# PowerSupply.net
KiCad netlist of a schematic drawn in Altium Designer
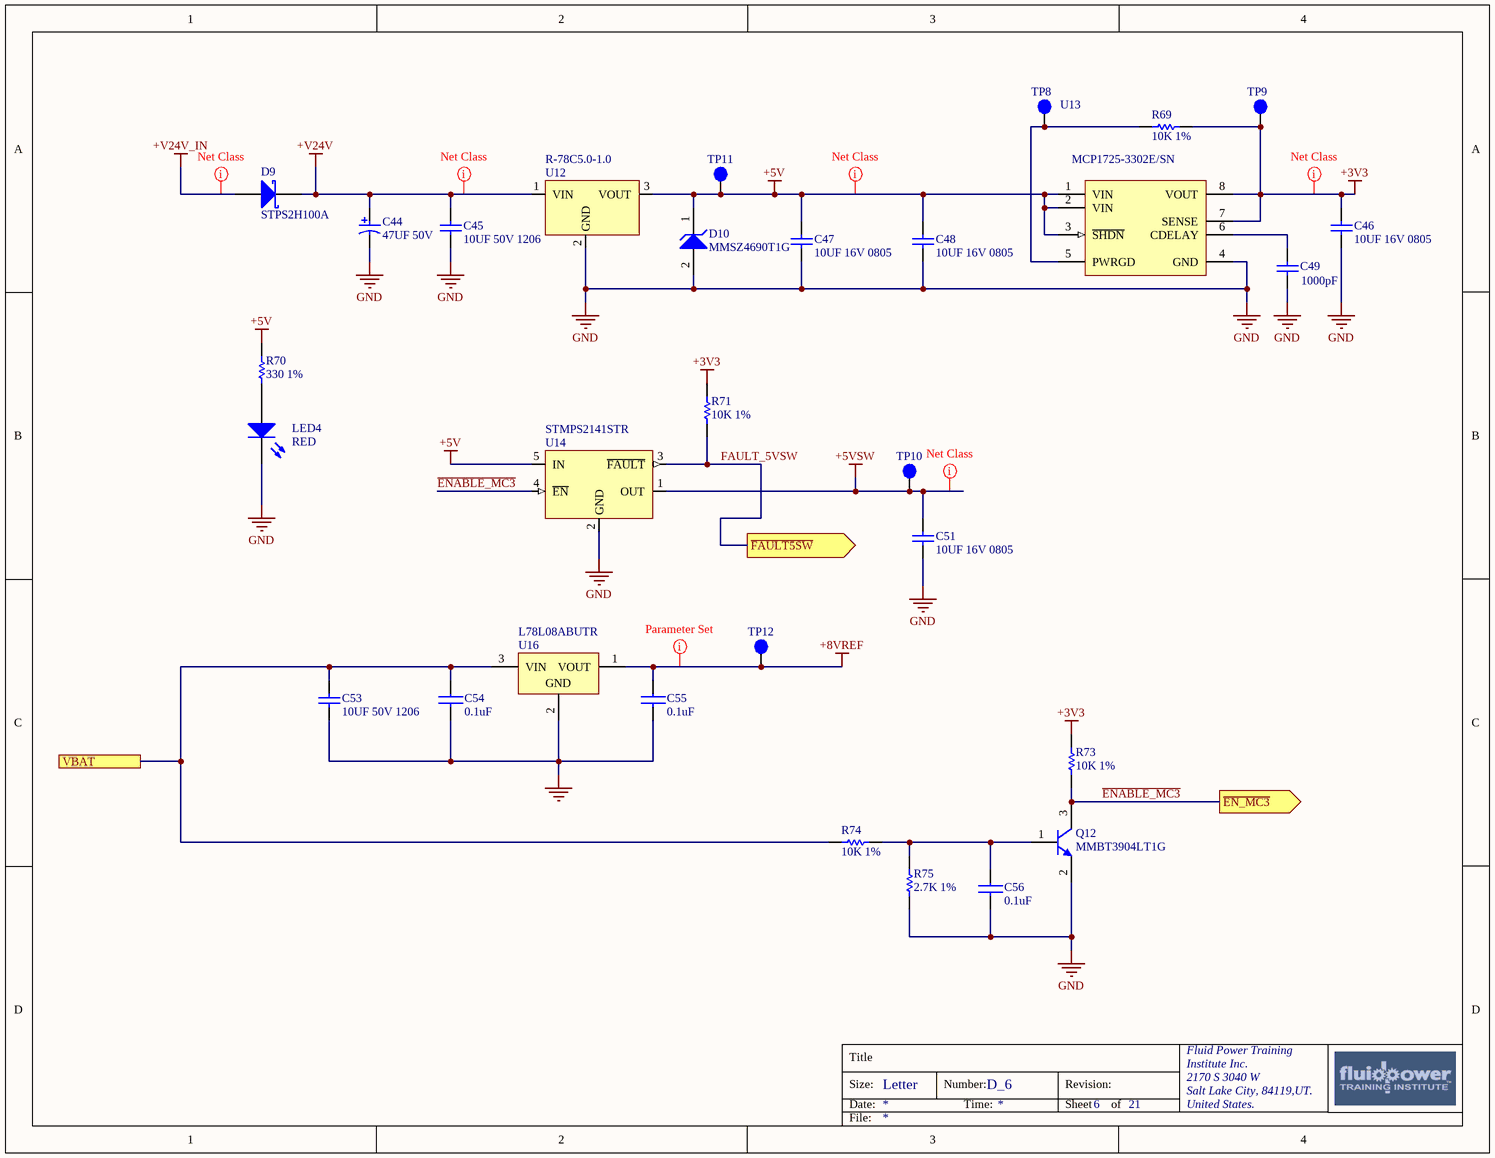
[diagram p0: PowerSupply.SchDoc]

(export (version "E")
  (design (tool "Eeschema 10.0.6"))
  (components
    (comp (ref "C44")
      (value "47UF 50V")
      (footprint "MC1:PNSC-EEE-HA1H470XP-2_V")
      (description "EEE-HA Series 50 V 47 uF Ø 6.3 x 7.7 mm 105 °C SMT V-Chip Aluminum Electrolytic")
      (fields
        (field (name "MANUFACTURER") "Panasonic")
        (field (name "MANUFACTURER PART NUMBER") "EEE-HA1H470XP")
      )
      (libsource (lib "MC1") (part "EEE-HA1H470XP"))
    )
    (comp (ref "C45")
      (value "10UF 50V 1206")
      (footprint "MC1:CAPC3216X180X20ML20")
      (description "CAP CER 10UF 50V X5R 1206")
      (fields
        (field (name "MANUFACTURER") "TDK")
        (field (name "MANUFACTURER PART NUMBER") "C3216X5R1H106K160AB")
      )
      (libsource (lib "MC1") (part "C3216X5R1H106K160AB"))
    )
    (comp (ref "C46")
      (value "10UF 16V 0805")
      (footprint "MC1:CAPC2012X14M")
      (description "CAP CER 10UF 16V X5R 0805")
      (fields
        (field (name "MANUFACTURER") "Murata")
        (field (name "MANUFACTURER PART NUMBER") "GRM21BR61C106KE15L")
      )
      (libsource (lib "MC1") (part "GRM21BR61C106KE15L"))
    )
    (comp (ref "C47")
      (value "10UF 16V 0805")
      (footprint "MC1:CAPC2012X14M")
      (description "CAP CER 10UF 16V X5R 0805")
      (fields
        (field (name "MANUFACTURER") "Murata")
        (field (name "MANUFACTURER PART NUMBER") "GRM21BR61C106KE15L")
      )
      (libsource (lib "MC1") (part "GRM21BR61C106KE15L"))
    )
    (comp (ref "C48")
      (value "10UF 16V 0805")
      (footprint "MC1:CAPC2012X14M")
      (description "CAP CER 10UF 16V X5R 0805")
      (fields
        (field (name "MANUFACTURER") "Murata")
        (field (name "MANUFACTURER PART NUMBER") "GRM21BR61C106KE15L")
      )
      (libsource (lib "MC1") (part "GRM21BR61C106KE15L"))
    )
    (comp (ref "C49")
      (value "1000pF")
      (footprint "C0805")
      (description "MLCC, 1000 pF, - 10%, X7R, 100 V, 0805 [2012 Metric] RoHS Compliant: Yes")
      (fields
        (field (name "MANUFACTURER") "KEMET")
        (field (name "MANUFACTURER PART NUMBER") "C0805C102K1RACTU")
      )
      (libsource (lib "MCx") (part "C0805C102K1RACTU"))
    )
    (comp (ref "C51")
      (value "10UF 16V 0805")
      (footprint "MC1:CAPC2012X14M")
      (description "CAP CER 10UF 16V X5R 0805")
      (fields
        (field (name "MANUFACTURER") "Murata")
        (field (name "MANUFACTURER PART NUMBER") "GRM21BR61C106KE15L")
      )
      (libsource (lib "MC1") (part "GRM21BR61C106KE15L"))
    )
    (comp (ref "C53")
      (value "10UF 50V 1206")
      (footprint "MC1:CAPC3216X180X20ML20")
      (description "CAP CER 10UF 50V X5R 1206")
      (fields
        (field (name "MANUFACTURER") "TDK")
        (field (name "MANUFACTURER PART NUMBER") "C3216X5R1H106K160AB")
      )
      (libsource (lib "MC1") (part "C3216X5R1H106K160AB"))
    )
    (comp (ref "C54")
      (value "0.1uF")
      (footprint "C0805")
      (description "Cap Ceramic 0.1uF 50V X7R 10% SMD 2.0 x 1.2 mm 125 C Paper T/R")
      (fields
        (field (name "MANUFACTURER") "KEMET")
        (field (name "MANUFACTURER PART NUMBER") "C0805C104K5RACTU")
      )
      (libsource (lib "MCx") (part "C0805C104K5RACTU"))
    )
    (comp (ref "C55")
      (value "0.1uF")
      (footprint "C0805")
      (description "Cap Ceramic 0.1uF 50V X7R 10% SMD 2.0 x 1.2 mm 125 C Paper T/R")
      (fields
        (field (name "MANUFACTURER") "KEMET")
        (field (name "MANUFACTURER PART NUMBER") "C0805C104K5RACTU")
      )
      (libsource (lib "MCx") (part "C0805C104K5RACTU"))
    )
    (comp (ref "C56")
      (value "0.1uF")
      (footprint "C0805")
      (description "Cap Ceramic 0.1uF 50V X7R 10% SMD 2.0 x 1.2 mm 125 C Paper T/R")
      (fields
        (field (name "MANUFACTURER") "KEMET")
        (field (name "MANUFACTURER PART NUMBER") "C0805C104K5RACTU")
      )
      (libsource (lib "MCx") (part "C0805C104K5RACTU"))
    )
    (comp (ref "D9")
      (value "STPS2H100A")
      (footprint "MC1:STM-SMA-2_V")
      (description "DIODE SCHOTTKY 100V 2A SMA")
      (fields (field (name "MANUFACTURER") "STMicroelectronics"))
      (libsource (lib "MC1") (part "STPS2H100A"))
    )
    (comp (ref "D10")
      (value "MMSZ4690T1G")
      (footprint "MC1:ONSC-SOD-123-2-425-04_V")
      (description "DIODE ZENER 5.6V 500MW SOD123")
      (fields (field (name "MANUFACTURER") "ON Semiconductor") (field (name "TOLERANCE") "5%"))
      (libsource (lib "MC1") (part "MMSZ4690T1G"))
    )
    (comp (ref "LED4")
      (value "RED")
      (footprint "LED0805")
      (description "LED RED CLEAR 0805 SMD")
      (fields
        (field (name "MANUFACTURER") "Wurth Electronics")
        (field (name "MANUFACTURER PART NUMBER") "150080RS75000")
      )
      (libsource (lib "MCx") (part "150080RS75000"))
    )
    (comp (ref "Q12")
      (value "MMBT3904LT1G")
      (footprint "MC1:ONSC-SOT-23-3-318-08_V")
      (description "ON Semi MMBT3904LT1G NPN Bipolar Transistor, 0.2 A, 40 V, 3-Pin SOT-23")
      (fields (field (name "MANUFACTURER") "ON Semiconductor"))
      (libsource (lib "MC1") (part "MMBT3904LT1G"))
    )
    (comp (ref "R69")
      (value "10K 1%")
      (footprint "R0805")
      (fields
        (field (name "MANUFACTURER") "Vishay")
        (field (name "MANUFACTURER PART NUMBER") "CRCW080510K0FKEA")
        (field (name "TOLERANCE") "1%")
      )
      (libsource (lib "MCx") (part "CRCW080510K0FKEA"))
    )
    (comp (ref "R70")
      (value "330 1%")
      (footprint "R0805")
      (description "RES SMD 330 OHM 1% 1/8W 0805")
      (fields
        (field (name "MANUFACTURER") "Panasonic")
        (field (name "MANUFACTURER PART NUMBER") "ERJ-6ENF3300V")
      )
      (libsource (lib "MCx") (part "ERJ-6ENF3300V"))
    )
    (comp (ref "R71")
      (value "10K 1%")
      (footprint "R0805")
      (fields
        (field (name "MANUFACTURER") "Vishay")
        (field (name "MANUFACTURER PART NUMBER") "CRCW080510K0FKEA")
        (field (name "TOLERANCE") "1%")
      )
      (libsource (lib "MCx") (part "CRCW080510K0FKEA"))
    )
    (comp (ref "R73")
      (value "10K 1%")
      (footprint "R0805")
      (fields
        (field (name "MANUFACTURER") "Vishay")
        (field (name "MANUFACTURER PART NUMBER") "CRCW080510K0FKEA")
        (field (name "TOLERANCE") "1%")
      )
      (libsource (lib "MCx") (part "CRCW080510K0FKEA"))
    )
    (comp (ref "R74")
      (value "10K 1%")
      (footprint "R0805")
      (fields
        (field (name "MANUFACTURER") "Vishay")
        (field (name "MANUFACTURER PART NUMBER") "CRCW080510K0FKEA")
        (field (name "TOLERANCE") "1%")
      )
      (libsource (lib "MCx") (part "CRCW080510K0FKEA"))
    )
    (comp (ref "R75")
      (value "2.7K 1%")
      (footprint "R0805")
      (description "RES SMD 2.7K OHM 1% 1/8W 0805")
      (fields
        (field (name "MANUFACTURER") "Yageo")
        (field (name "MANUFACTURER PART NUMBER") "AC0805FR-072K7L")
      )
      (libsource (lib "MCx") (part "AC0805FR-072K7L"))
    )
    (comp (ref "TP8")
      (value "T")
      (footprint "MC1:TESTPOINTSMD_1x1MM")
      (description "SMD Test Point")
      (libsource (lib "MC1") (part "TestPoint_SMD_1x1"))
    )
    (comp (ref "TP9")
      (value "T")
      (footprint "MC1:TESTPOINTSMD_1x1MM")
      (description "SMD Test Point")
      (libsource (lib "MC1") (part "TestPoint_SMD_1x1"))
    )
    (comp (ref "TP10")
      (value "T")
      (footprint "MC1:TESTPOINTSMD_1x1MM")
      (description "SMD Test Point")
      (libsource (lib "MC1") (part "TestPoint_SMD_1x1"))
    )
    (comp (ref "TP11")
      (value "T")
      (footprint "MC1:TESTPOINTSMD_1x1MM")
      (description "SMD Test Point")
      (libsource (lib "MC1") (part "TestPoint_SMD_1x1"))
    )
    (comp (ref "TP12")
      (value "T")
      (footprint "MC1:TESTPOINTSMD_1x1MM")
      (description "SMD Test Point")
      (libsource (lib "MC1") (part "TestPoint_SMD_1x1"))
    )
    (comp (ref "U12")
      (value "R-78C5.0-1.0")
      (footprint "MC1:SIP3")
      (description "DC DC CONVERTER 5V 5W")
      (fields (field (name "MANUFACTURER") "Recom"))
      (libsource (lib "MC1") (part "R-78C5.0-1.0"))
    )
    (comp (ref "U13")
      (value "MCP1725-3302E/SN")
      (footprint "MC1:SOIC-SN8_M")
      (description "IC REG LINEAR 3.3V 500MA 8SOIC")
      (fields (field (name "MANUFACTURER") "Microchip"))
      (libsource (lib "MC1") (part "MCP1725-3302E/SN"))
    )
    (comp (ref "U14")
      (value "STMPS2141STR")
      (footprint "MC1:SOT95P280X145-5M")
      (description "IC PWR SWITCH 1CH 500MA SOT23-5")
      (fields (field (name "MANUFACTURER") "STMicroelectronics") (field (name "VOLTAGE") "5.5V"))
      (libsource (lib "MC1") (part "STMPS2141STR"))
    )
    (comp (ref "U16")
      (value "L78L08ABUTR")
      (footprint "SOT-89_L")
      (fields (field (name "MANUFACTURER") "STMicroelectronics"))
      (libsource (lib "MCx") (part "L78L08ABUTR"))
    )
  )
  (nets
    (net (code "1") (name "+3V3") (class "Default")
      (node (ref "C46") (pin "2") (pinfunction "2_2") (pintype "passive"))
      (node (ref "R69") (pin "2") (pinfunction "2_2") (pintype "passive"))
      (node (ref "R71") (pin "2") (pinfunction "2_2") (pintype "passive"))
      (node (ref "R73") (pin "2") (pinfunction "2_2") (pintype "passive"))
      (node (ref "TP9") (pin "1") (pinfunction "1_1") (pintype "passive"))
      (node (ref "U13") (pin "7") (pinfunction "SENSE_7") (pintype "passive"))
      (node (ref "U13") (pin "8") (pinfunction "VOUT_8") (pintype "power_in"))
    )
    (net (code "2") (name "+5V") (class "Default")
      (node (ref "C47") (pin "2") (pinfunction "2_2") (pintype "passive"))
      (node (ref "C48") (pin "2") (pinfunction "2_2") (pintype "passive"))
      (node (ref "D10") (pin "1") (pinfunction "K_1") (pintype "passive"))
      (node (ref "R70") (pin "2") (pinfunction "2_2") (pintype "passive"))
      (node (ref "TP11") (pin "1") (pinfunction "1_1") (pintype "passive"))
      (node (ref "U12") (pin "3") (pinfunction "VOUT_3") (pintype "power_in"))
      (node (ref "U13") (pin "1") (pinfunction "VIN_1") (pintype "power_in"))
      (node (ref "U13") (pin "2") (pinfunction "VIN_2") (pintype "power_in"))
      (node (ref "U13") (pin "3") (pinfunction "~{SHDN}_3") (pintype "input"))
      (node (ref "U14") (pin "5") (pinfunction "IN_5") (pintype "power_in"))
    )
    (net (code "3") (name "+5VSW") (class "Default")
      (node (ref "C51") (pin "2") (pinfunction "2_2") (pintype "passive"))
      (node (ref "TP10") (pin "1") (pinfunction "1_1") (pintype "passive"))
      (node (ref "U14") (pin "1") (pinfunction "OUT_1") (pintype "power_in"))
    )
    (net (code "4") (name "+8VREF") (class "Default")
      (node (ref "C55") (pin "1") (pinfunction "1_1") (pintype "passive"))
      (node (ref "TP12") (pin "1") (pinfunction "1_1") (pintype "passive"))
      (node (ref "U16") (pin "1") (pinfunction "VOUT_1") (pintype "power_in"))
    )
    (net (code "5") (name "+V24V") (class "Default")
      (node (ref "C44") (pin "1") (pinfunction "1_1") (pintype "passive"))
      (node (ref "C45") (pin "2") (pinfunction "2_2") (pintype "passive"))
      (node (ref "D9") (pin "2") (pinfunction "K_2") (pintype "passive"))
      (node (ref "U12") (pin "1") (pinfunction "VIN_1") (pintype "power_in"))
    )
    (net (code "6") (name "+V24V_IN") (class "Default")
      (node (ref "D9") (pin "1") (pinfunction "A_1") (pintype "passive"))
    )
    (net (code "7") (name "/FAULT_5VSW") (class "Default")
      (node (ref "R71") (pin "1") (pinfunction "1_1") (pintype "passive"))
      (node (ref "U14") (pin "3") (pinfunction "~{FAULT}_3") (pintype "output"))
    )
    (net (code "8") (name "/VBAT") (class "Default")
      (node (ref "C53") (pin "2") (pinfunction "2_2") (pintype "passive"))
      (node (ref "C54") (pin "1") (pinfunction "1_1") (pintype "passive"))
      (node (ref "R74") (pin "1") (pinfunction "1_1") (pintype "passive"))
      (node (ref "U16") (pin "3") (pinfunction "VIN_3") (pintype "power_in"))
    )
    (net (code "9") (name "/~{ENABLE_MC3}") (class "Default")
      (node (ref "Q12") (pin "3") (pinfunction "C_3") (pintype "passive"))
      (node (ref "R73") (pin "1") (pinfunction "1_1") (pintype "passive"))
      (node (ref "U14") (pin "4") (pinfunction "~{EN}_4") (pintype "input"))
    )
    (net (code "10") (name "GND") (class "Default")
      (node (ref "C44") (pin "2") (pinfunction "2_2") (pintype "passive"))
      (node (ref "C45") (pin "1") (pinfunction "1_1") (pintype "passive"))
      (node (ref "C46") (pin "1") (pinfunction "1_1") (pintype "passive"))
      (node (ref "C47") (pin "1") (pinfunction "1_1") (pintype "passive"))
      (node (ref "C48") (pin "1") (pinfunction "1_1") (pintype "passive"))
      (node (ref "C49") (pin "1") (pinfunction "1_1") (pintype "passive"))
      (node (ref "C51") (pin "1") (pinfunction "1_1") (pintype "passive"))
      (node (ref "C53") (pin "1") (pinfunction "1_1") (pintype "passive"))
      (node (ref "C54") (pin "2") (pinfunction "2_2") (pintype "passive"))
      (node (ref "C55") (pin "2") (pinfunction "2_2") (pintype "passive"))
      (node (ref "C56") (pin "2") (pinfunction "2_2") (pintype "passive"))
      (node (ref "D10") (pin "2") (pinfunction "A_2") (pintype "passive"))
      (node (ref "LED4") (pin "1") (pinfunction "K_1") (pintype "passive"))
      (node (ref "Q12") (pin "2") (pinfunction "E_2") (pintype "passive"))
      (node (ref "R75") (pin "1") (pinfunction "1_1") (pintype "passive"))
      (node (ref "U12") (pin "2") (pinfunction "GND_2") (pintype "power_in"))
      (node (ref "U13") (pin "4") (pinfunction "GND_4") (pintype "power_in"))
      (node (ref "U14") (pin "2") (pinfunction "GND_2") (pintype "power_in"))
      (node (ref "U16") (pin "2") (pinfunction "GND_2") (pintype "power_in"))
    )
    (net (code "11") (name "Net-(LED4-A)") (class "Default")
      (node (ref "LED4") (pin "2") (pinfunction "A_2") (pintype "passive"))
      (node (ref "R70") (pin "1") (pinfunction "1_1") (pintype "passive"))
    )
    (net (code "12") (name "Net-(Q12-B)") (class "Default")
      (node (ref "C56") (pin "1") (pinfunction "1_1") (pintype "passive"))
      (node (ref "Q12") (pin "1") (pinfunction "B_1") (pintype "passive"))
      (node (ref "R74") (pin "2") (pinfunction "2_2") (pintype "passive"))
      (node (ref "R75") (pin "2") (pinfunction "2_2") (pintype "passive"))
    )
    (net (code "13") (name "Net-(U13-CDELAY)") (class "Default")
      (node (ref "C49") (pin "2") (pinfunction "2_2") (pintype "passive"))
      (node (ref "U13") (pin "6") (pinfunction "CDELAY_6") (pintype "passive"))
    )
    (net (code "14") (name "Net-(U13-PWRGD)") (class "Default")
      (node (ref "R69") (pin "1") (pinfunction "1_1") (pintype "passive"))
      (node (ref "TP8") (pin "1") (pinfunction "1_1") (pintype "passive"))
      (node (ref "U13") (pin "5") (pinfunction "PWRGD_5") (pintype "power_in"))
    )
  )
)
